# 282_Universal_Verteilerplatine_ALF_v1_0_.net
KiCad netlist of a schematic drawn in EAGLE
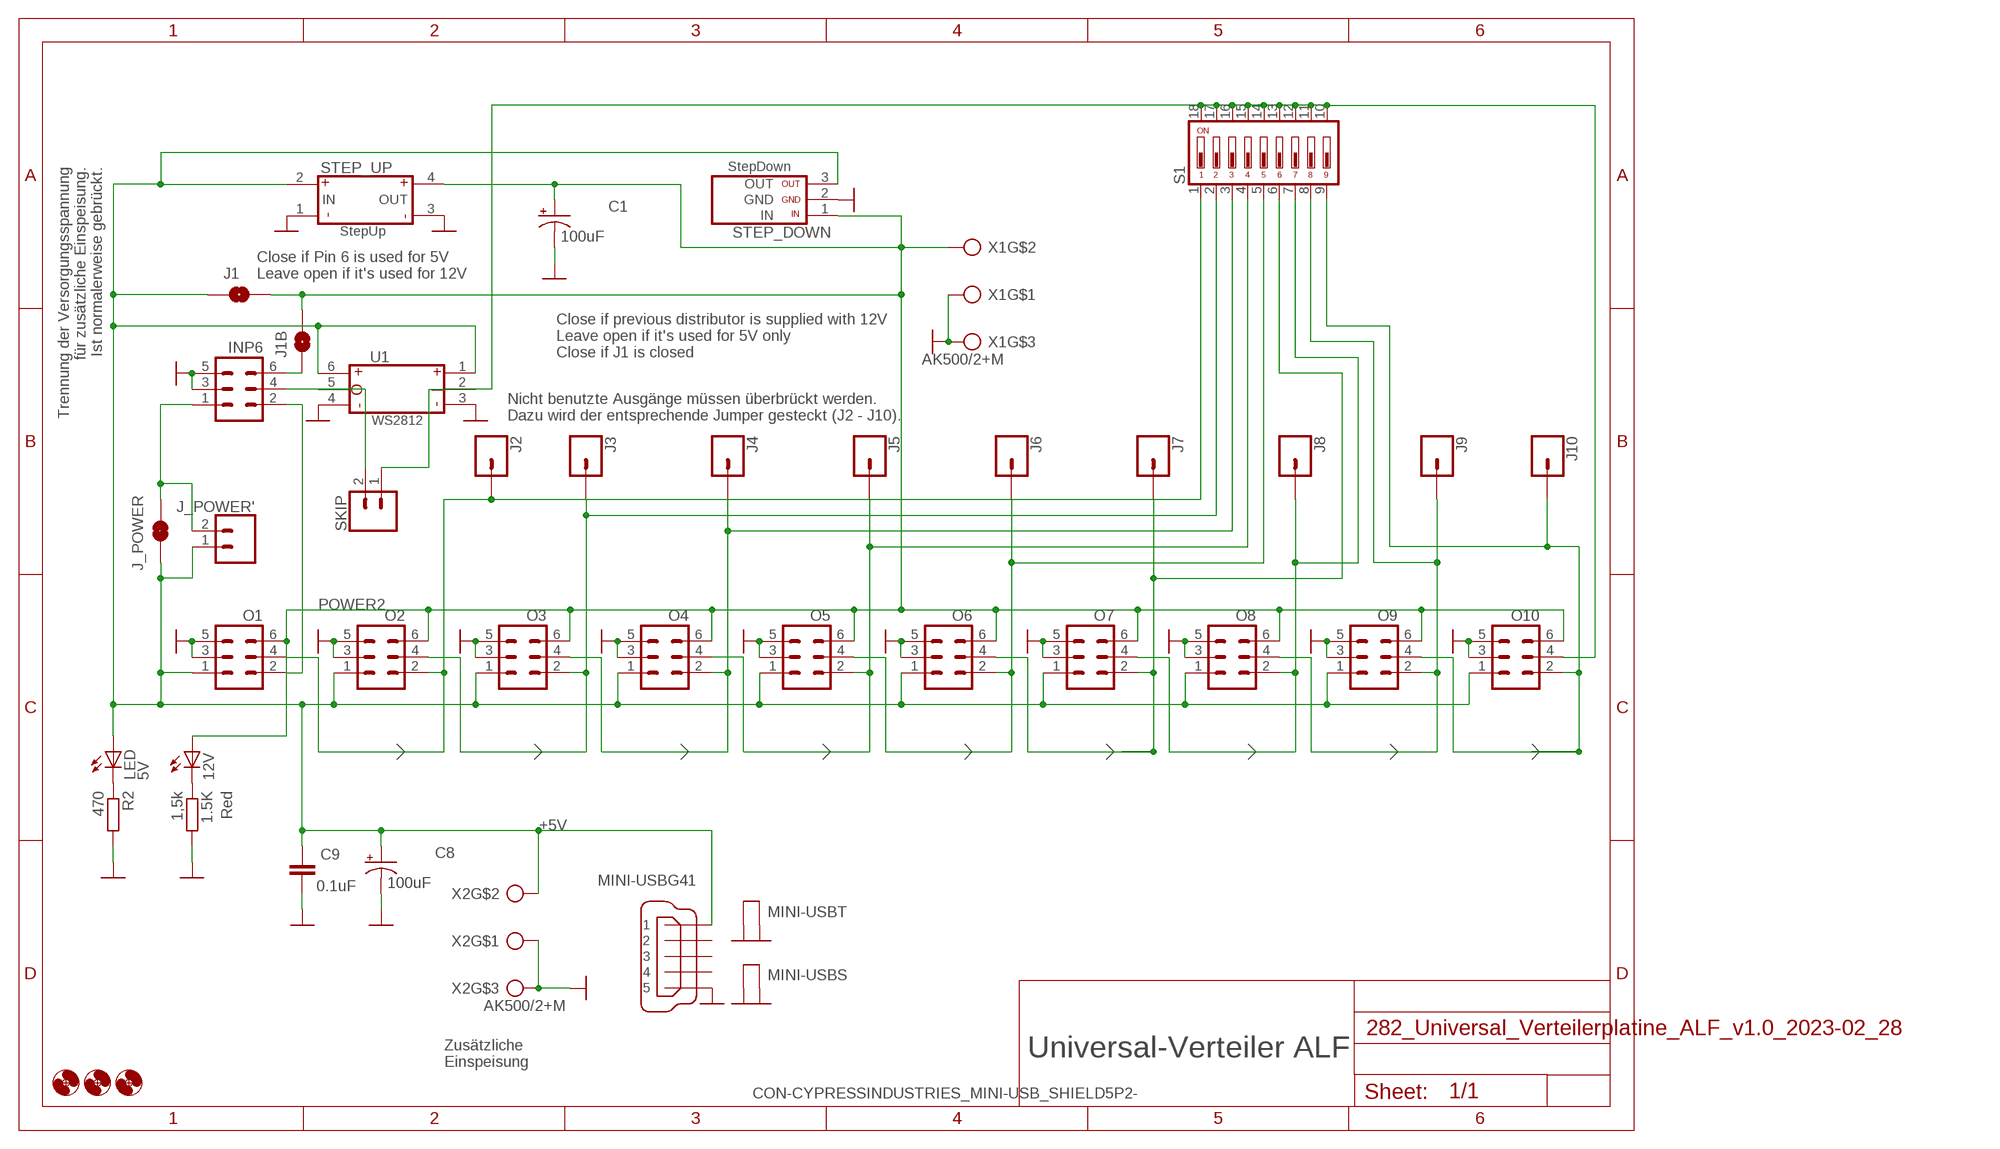
[diagram p0: schematic, sheet 1]

(export (version "E")
  (design (tool "Eeschema 10.0.6"))
  (components
    (comp (ref "1.5K")
      (value "1,5k")
      (footprint "eagle-import:RCL_0207_7")
      (libsource (lib "eagle-import") (part "RCL_R-EU_0207/7"))
    )
    (comp (ref "12V")
      (value "Red")
      (footprint "eagle-import:LED_LED3MM")
      (libsource (lib "eagle-import") (part "LED_LED3MM"))
    )
    (comp (ref "C1")
      (value "100uF")
      (footprint "eagle-import:SPARKFUN-CAPACITORS_CPOL-RADIAL-100UF-25V")
      (libsource (lib "eagle-import") (part "SPARKFUN-CAPACITORS_100UF-25V-20%(PTH)"))
    )
    (comp (ref "C8")
      (value "100uF")
      (footprint "eagle-import:SPARKFUN-CAPACITORS_CPOL-RADIAL-100UF-25V")
      (libsource (lib "eagle-import") (part "SPARKFUN-CAPACITORS_100UF-25V-20%(PTH)"))
    )
    (comp (ref "C9")
      (value "0.1uF")
      (footprint "eagle-import:C025-025X050")
      (libsource (lib "eagle-import") (part "C-EU025-025X050"))
    )
    (comp (ref "H5")
      (value "MOUNT-HOLE3.0")
      (footprint "eagle-import:3,0")
      (libsource (lib "eagle-import") (part "MOUNT-HOLE3.0"))
    )
    (comp (ref "H6")
      (value "MOUNT-HOLE3.0")
      (footprint "eagle-import:3,0")
      (libsource (lib "eagle-import") (part "MOUNT-HOLE3.0"))
    )
    (comp (ref "H8")
      (value "MOUNT-HOLE3.0")
      (footprint "eagle-import:3,0")
      (libsource (lib "eagle-import") (part "MOUNT-HOLE3.0"))
    )
    (comp (ref "INP6")
      (value "ML6")
      (footprint "eagle-import:ML6")
      (libsource (lib "eagle-import") (part "ML6"))
    )
    (comp (ref "J1")
      (value "SOLDERJUMPERNO")
      (footprint "eagle-import:SJ_2S-NO")
      (libsource (lib "eagle-import") (part "SOLDERJUMPERNO"))
    )
    (comp (ref "J1B")
      (value "SOLDERJUMPERNO")
      (footprint "eagle-import:SJ_2S-NO")
      (libsource (lib "eagle-import") (part "SOLDERJUMPERNO"))
    )
    (comp (ref "J2")
      (value "CONN_01_NO_BORDER")
      (footprint "eagle-import:1X01_NO_BORDER")
      (libsource (lib "eagle-import") (part "CONN_01_NO_BORDER"))
    )
    (comp (ref "J3")
      (value "CONN_01_NO_BORDER")
      (footprint "eagle-import:1X01_NO_BORDER")
      (libsource (lib "eagle-import") (part "CONN_01_NO_BORDER"))
    )
    (comp (ref "J4")
      (value "CONN_01_NO_BORDER")
      (footprint "eagle-import:1X01_NO_BORDER")
      (libsource (lib "eagle-import") (part "CONN_01_NO_BORDER"))
    )
    (comp (ref "J5")
      (value "CONN_01_NO_BORDER")
      (footprint "eagle-import:1X01_NO_BORDER")
      (libsource (lib "eagle-import") (part "CONN_01_NO_BORDER"))
    )
    (comp (ref "J6")
      (value "CONN_01_NO_BORDER")
      (footprint "eagle-import:1X01_NO_BORDER")
      (libsource (lib "eagle-import") (part "CONN_01_NO_BORDER"))
    )
    (comp (ref "J7")
      (value "CONN_01_NO_BORDER")
      (footprint "eagle-import:1X01_NO_BORDER")
      (libsource (lib "eagle-import") (part "CONN_01_NO_BORDER"))
    )
    (comp (ref "J8")
      (value "CONN_01_NO_BORDER")
      (footprint "eagle-import:1X01_NO_BORDER")
      (libsource (lib "eagle-import") (part "CONN_01_NO_BORDER"))
    )
    (comp (ref "J9")
      (value "CONN_01_NO_BORDER")
      (footprint "eagle-import:1X01_NO_BORDER")
      (libsource (lib "eagle-import") (part "CONN_01_NO_BORDER"))
    )
    (comp (ref "J10")
      (value "CONN_01_NO_BORDER")
      (footprint "eagle-import:1X01_NO_BORDER")
      (libsource (lib "eagle-import") (part "CONN_01_NO_BORDER"))
    )
    (comp (ref "J_POWER")
      (value "SOLDERJUMPERNO")
      (footprint "eagle-import:SJ_2S-NO")
      (libsource (lib "eagle-import") (part "SOLDERJUMPERNO"))
    )
    (comp (ref "J_POWER'")
      (value "CONN_02")
      (footprint "eagle-import:1X02")
      (libsource (lib "eagle-import") (part "CONN_02"))
    )
    (comp (ref "LED")
      (value "5V")
      (footprint "eagle-import:LED_LED3MM")
      (libsource (lib "eagle-import") (part "LED_LED3MM"))
    )
    (comp (ref "MINI-USB")
      (value "CON-CYPRESSINDUSTRIES_MINI-USB_SHIELD5P2-")
      (footprint "eagle-import:MINI_USB_MULTI")
      (libsource (lib "eagle-import") (part "CON-CYPRESSINDUSTRIES_MINI-USB_SHIELD5P2-"))
    )
    (comp (ref "O1")
      (value "ML6")
      (footprint "eagle-import:ML6")
      (libsource (lib "eagle-import") (part "ML6"))
    )
    (comp (ref "O2")
      (value "ML6")
      (footprint "eagle-import:ML6")
      (libsource (lib "eagle-import") (part "ML6"))
    )
    (comp (ref "O3")
      (value "ML6")
      (footprint "eagle-import:ML6")
      (libsource (lib "eagle-import") (part "ML6"))
    )
    (comp (ref "O4")
      (value "ML6")
      (footprint "eagle-import:ML6")
      (libsource (lib "eagle-import") (part "ML6"))
    )
    (comp (ref "O5")
      (value "ML6")
      (footprint "eagle-import:ML6")
      (libsource (lib "eagle-import") (part "ML6"))
    )
    (comp (ref "O6")
      (value "ML6")
      (footprint "eagle-import:ML6")
      (libsource (lib "eagle-import") (part "ML6"))
    )
    (comp (ref "O7")
      (value "ML6")
      (footprint "eagle-import:ML6")
      (libsource (lib "eagle-import") (part "ML6"))
    )
    (comp (ref "O8")
      (value "ML6")
      (footprint "eagle-import:ML6")
      (libsource (lib "eagle-import") (part "ML6"))
    )
    (comp (ref "O9")
      (value "ML6")
      (footprint "eagle-import:ML6")
      (libsource (lib "eagle-import") (part "ML6"))
    )
    (comp (ref "O10")
      (value "ML6")
      (footprint "eagle-import:ML6")
      (libsource (lib "eagle-import") (part "ML6"))
    )
    (comp (ref "R2")
      (value "470")
      (footprint "eagle-import:RCL_0207_7")
      (libsource (lib "eagle-import") (part "RCL_R-EU_0207/7"))
    )
    (comp (ref "S1")
      (value "DIP09YL")
      (footprint "eagle-import:DIP09YL")
      (libsource (lib "eagle-import") (part "DIP09YL"))
    )
    (comp (ref "SKIP")
      (value "CONN_02")
      (footprint "eagle-import:1X02")
      (libsource (lib "eagle-import") (part "CONN_02"))
    )
    (comp (ref "STEP_DOWN")
      (value "STEP_DOWN")
      (footprint "eagle-import:MINI_STEP_DOWN")
      (libsource (lib "eagle-import") (part "STEP_DOWN"))
    )
    (comp (ref "STEP_UP")
      (value "STEP_UP")
      (footprint "eagle-import:MINI_STEP_UP")
      (libsource (lib "eagle-import") (part "STEP_UP"))
    )
    (comp (ref "U1")
      (value "WS2812_BREAKOUTCUT")
      (footprint "eagle-import:WS2812__BREAKOUT_CUT")
      (libsource (lib "eagle-import") (part "WS2812_BREAKOUTCUT"))
    )
    (comp (ref "X1")
      (value "AK500/2+M")
      (footprint "eagle-import:AK500_2+M")
      (libsource (lib "eagle-import") (part "AK500/2+M"))
    )
    (comp (ref "X2")
      (value "AK500/2+M")
      (footprint "eagle-import:AK500_2+M")
      (libsource (lib "eagle-import") (part "AK500/2+M"))
    )
  )
  (nets
    (net (code "1") (name "/POWER2") (class "Default")
      (node (ref "12V") (pin "A") (pinfunction "A_A") (pintype "passive"))
      (node (ref "C1") (pin "1") (pinfunction "+_1") (pintype "passive"))
      (node (ref "J1") (pin "2") (pinfunction "2_2") (pintype "passive"))
      (node (ref "J1B") (pin "2") (pinfunction "2_2") (pintype "passive"))
      (node (ref "O1") (pin "6") (pinfunction "6_6") (pintype "passive"))
      (node (ref "O10") (pin "6") (pinfunction "6_6") (pintype "passive"))
      (node (ref "O2") (pin "6") (pinfunction "6_6") (pintype "passive"))
      (node (ref "O3") (pin "6") (pinfunction "6_6") (pintype "passive"))
      (node (ref "O4") (pin "6") (pinfunction "6_6") (pintype "passive"))
      (node (ref "O5") (pin "6") (pinfunction "6_6") (pintype "passive"))
      (node (ref "O6") (pin "6") (pinfunction "6_6") (pintype "passive"))
      (node (ref "O7") (pin "6") (pinfunction "6_6") (pintype "passive"))
      (node (ref "O8") (pin "6") (pinfunction "6_6") (pintype "passive"))
      (node (ref "O9") (pin "6") (pinfunction "6_6") (pintype "passive"))
      (node (ref "STEP_DOWN") (pin "1") (pinfunction "VDD_IN_1") (pintype "passive"))
      (node (ref "STEP_UP") (pin "4") (pinfunction "VDD_OUT_4") (pintype "passive"))
      (node (ref "X1") (pin "2") (pinfunction "KL_2") (pintype "passive"))
    )
    (net (code "2") (name "GND") (class "Default")
      (node (ref "1.5K") (pin "2") (pinfunction "2_2") (pintype "passive"))
      (node (ref "C1") (pin "2") (pinfunction "-_2") (pintype "passive"))
      (node (ref "C8") (pin "2") (pinfunction "-_2") (pintype "passive"))
      (node (ref "C9") (pin "1") (pinfunction "1_1") (pintype "passive"))
      (node (ref "INP6") (pin "3") (pinfunction "3_3") (pintype "passive"))
      (node (ref "INP6") (pin "5") (pinfunction "5_5") (pintype "passive"))
      (node (ref "MINI-USB") (pin "5") (pinfunction "5_5") (pintype "passive"))
      (node (ref "MINI-USB") (pin "M1") (pinfunction "S1_M1") (pintype "passive"))
      (node (ref "MINI-USB") (pin "M2") (pinfunction "S2_M2") (pintype "passive"))
      (node (ref "MINI-USB") (pin "M3") (pinfunction "S1_M3") (pintype "passive"))
      (node (ref "MINI-USB") (pin "M4") (pinfunction "S2_M4") (pintype "passive"))
      (node (ref "O1") (pin "3") (pinfunction "3_3") (pintype "passive"))
      (node (ref "O1") (pin "5") (pinfunction "5_5") (pintype "passive"))
      (node (ref "O10") (pin "3") (pinfunction "3_3") (pintype "passive"))
      (node (ref "O10") (pin "5") (pinfunction "5_5") (pintype "passive"))
      (node (ref "O2") (pin "3") (pinfunction "3_3") (pintype "passive"))
      (node (ref "O2") (pin "5") (pinfunction "5_5") (pintype "passive"))
      (node (ref "O3") (pin "3") (pinfunction "3_3") (pintype "passive"))
      (node (ref "O3") (pin "5") (pinfunction "5_5") (pintype "passive"))
      (node (ref "O4") (pin "3") (pinfunction "3_3") (pintype "passive"))
      (node (ref "O4") (pin "5") (pinfunction "5_5") (pintype "passive"))
      (node (ref "O5") (pin "3") (pinfunction "3_3") (pintype "passive"))
      (node (ref "O5") (pin "5") (pinfunction "5_5") (pintype "passive"))
      (node (ref "O6") (pin "3") (pinfunction "3_3") (pintype "passive"))
      (node (ref "O6") (pin "5") (pinfunction "5_5") (pintype "passive"))
      (node (ref "O7") (pin "3") (pinfunction "3_3") (pintype "passive"))
      (node (ref "O7") (pin "5") (pinfunction "5_5") (pintype "passive"))
      (node (ref "O8") (pin "3") (pinfunction "3_3") (pintype "passive"))
      (node (ref "O8") (pin "5") (pinfunction "5_5") (pintype "passive"))
      (node (ref "O9") (pin "3") (pinfunction "3_3") (pintype "passive"))
      (node (ref "O9") (pin "5") (pinfunction "5_5") (pintype "passive"))
      (node (ref "R2") (pin "2") (pinfunction "2_2") (pintype "passive"))
      (node (ref "STEP_DOWN") (pin "2") (pinfunction "GND_2") (pintype "passive"))
      (node (ref "STEP_UP") (pin "1") (pinfunction "GND_IN_1") (pintype "passive"))
      (node (ref "STEP_UP") (pin "3") (pinfunction "GND_OUT_3") (pintype "passive"))
      (node (ref "U1") (pin "3") (pinfunction "GND1_3") (pintype "passive"))
      (node (ref "U1") (pin "4") (pinfunction "GND_4") (pintype "passive"))
      (node (ref "X1") (pin "1") (pinfunction "KL_1") (pintype "passive"))
      (node (ref "X1") (pin "M") (pinfunction "KL_M") (pintype "passive"))
      (node (ref "X2") (pin "1") (pinfunction "KL_1") (pintype "passive"))
      (node (ref "X2") (pin "M") (pinfunction "KL_M") (pintype "passive"))
    )
    (net (code "3") (name "Net-(12V-C)") (class "Default")
      (node (ref "1.5K") (pin "1") (pinfunction "1_1") (pintype "passive"))
      (node (ref "12V") (pin "K") (pinfunction "C_K") (pintype "passive"))
    )
    (net (code "4") (name "Net-(C8-+)") (class "Default")
      (node (ref "C8") (pin "1") (pinfunction "+_1") (pintype "passive"))
      (node (ref "C9") (pin "2") (pinfunction "2_2") (pintype "passive"))
      (node (ref "J1") (pin "1") (pinfunction "1_1") (pintype "passive"))
      (node (ref "J_POWER") (pin "1") (pinfunction "1_1") (pintype "passive"))
      (node (ref "J_POWER'") (pin "1") (pinfunction "1_1") (pintype "passive"))
      (node (ref "LED") (pin "A") (pinfunction "A_A") (pintype "passive"))
      (node (ref "MINI-USB") (pin "1") (pinfunction "1_1") (pintype "passive"))
      (node (ref "O1") (pin "1") (pinfunction "1_1") (pintype "passive"))
      (node (ref "O10") (pin "1") (pinfunction "1_1") (pintype "passive"))
      (node (ref "O2") (pin "1") (pinfunction "1_1") (pintype "passive"))
      (node (ref "O3") (pin "1") (pinfunction "1_1") (pintype "passive"))
      (node (ref "O4") (pin "1") (pinfunction "1_1") (pintype "passive"))
      (node (ref "O5") (pin "1") (pinfunction "1_1") (pintype "passive"))
      (node (ref "O6") (pin "1") (pinfunction "1_1") (pintype "passive"))
      (node (ref "O7") (pin "1") (pinfunction "1_1") (pintype "passive"))
      (node (ref "O8") (pin "1") (pinfunction "1_1") (pintype "passive"))
      (node (ref "O9") (pin "1") (pinfunction "1_1") (pintype "passive"))
      (node (ref "STEP_DOWN") (pin "3") (pinfunction "VDD_OUT_3") (pintype "passive"))
      (node (ref "STEP_UP") (pin "2") (pinfunction "VDD_IN_2") (pintype "passive"))
      (node (ref "U1") (pin "1") (pinfunction "VDD1_1") (pintype "passive"))
      (node (ref "U1") (pin "6") (pinfunction "VDD_6") (pintype "passive"))
      (node (ref "X2") (pin "2") (pinfunction "KL_2") (pintype "passive"))
    )
    (net (code "5") (name "Net-(INP6-Pad1)") (class "Default")
      (node (ref "INP6") (pin "1") (pinfunction "1_1") (pintype "passive"))
      (node (ref "J_POWER") (pin "2") (pinfunction "2_2") (pintype "passive"))
      (node (ref "J_POWER'") (pin "2") (pinfunction "2_2") (pintype "passive"))
    )
    (net (code "6") (name "Net-(INP6-Pad2)") (class "Default")
      (node (ref "INP6") (pin "2") (pinfunction "2_2") (pintype "passive"))
      (node (ref "O1") (pin "2") (pinfunction "2_2") (pintype "passive"))
    )
    (net (code "7") (name "Net-(INP6-Pad6)") (class "Default")
      (node (ref "INP6") (pin "6") (pinfunction "6_6") (pintype "passive"))
      (node (ref "J1B") (pin "1") (pinfunction "1_1") (pintype "passive"))
    )
    (net (code "8") (name "Net-(J2-Pad1)") (class "Default")
      (node (ref "J2") (pin "1") (pinfunction "1_1") (pintype "passive"))
      (node (ref "O1") (pin "4") (pinfunction "4_4") (pintype "passive"))
      (node (ref "O2") (pin "2") (pinfunction "2_2") (pintype "passive"))
      (node (ref "S1") (pin "1") (pinfunction "1_1") (pintype "passive"))
    )
    (net (code "9") (name "Net-(J3-Pad1)") (class "Default")
      (node (ref "J3") (pin "1") (pinfunction "1_1") (pintype "passive"))
      (node (ref "O2") (pin "4") (pinfunction "4_4") (pintype "passive"))
      (node (ref "O3") (pin "2") (pinfunction "2_2") (pintype "passive"))
      (node (ref "S1") (pin "2") (pinfunction "2_2") (pintype "passive"))
    )
    (net (code "10") (name "Net-(J4-Pad1)") (class "Default")
      (node (ref "J4") (pin "1") (pinfunction "1_1") (pintype "passive"))
      (node (ref "O3") (pin "4") (pinfunction "4_4") (pintype "passive"))
      (node (ref "O4") (pin "2") (pinfunction "2_2") (pintype "passive"))
      (node (ref "S1") (pin "3") (pinfunction "3_3") (pintype "passive"))
    )
    (net (code "11") (name "Net-(J5-Pad1)") (class "Default")
      (node (ref "J5") (pin "1") (pinfunction "1_1") (pintype "passive"))
      (node (ref "O4") (pin "4") (pinfunction "4_4") (pintype "passive"))
      (node (ref "O5") (pin "2") (pinfunction "2_2") (pintype "passive"))
      (node (ref "S1") (pin "4") (pinfunction "4_4") (pintype "passive"))
    )
    (net (code "12") (name "Net-(J6-Pad1)") (class "Default")
      (node (ref "J6") (pin "1") (pinfunction "1_1") (pintype "passive"))
      (node (ref "O5") (pin "4") (pinfunction "4_4") (pintype "passive"))
      (node (ref "O6") (pin "2") (pinfunction "2_2") (pintype "passive"))
      (node (ref "S1") (pin "5") (pinfunction "5_5") (pintype "passive"))
    )
    (net (code "13") (name "Net-(J7-Pad1)") (class "Default")
      (node (ref "J7") (pin "1") (pinfunction "1_1") (pintype "passive"))
      (node (ref "O6") (pin "4") (pinfunction "4_4") (pintype "passive"))
      (node (ref "O7") (pin "2") (pinfunction "2_2") (pintype "passive"))
      (node (ref "S1") (pin "6") (pinfunction "6_6") (pintype "passive"))
    )
    (net (code "14") (name "Net-(J8-Pad1)") (class "Default")
      (node (ref "J8") (pin "1") (pinfunction "1_1") (pintype "passive"))
      (node (ref "O7") (pin "4") (pinfunction "4_4") (pintype "passive"))
      (node (ref "O8") (pin "2") (pinfunction "2_2") (pintype "passive"))
      (node (ref "S1") (pin "7") (pinfunction "7_7") (pintype "passive"))
    )
    (net (code "15") (name "Net-(J9-Pad1)") (class "Default")
      (node (ref "J9") (pin "1") (pinfunction "1_1") (pintype "passive"))
      (node (ref "O8") (pin "4") (pinfunction "4_4") (pintype "passive"))
      (node (ref "O9") (pin "2") (pinfunction "2_2") (pintype "passive"))
      (node (ref "S1") (pin "8") (pinfunction "8_8") (pintype "passive"))
    )
    (net (code "16") (name "Net-(J10-Pad1)") (class "Default")
      (node (ref "J10") (pin "1") (pinfunction "1_1") (pintype "passive"))
      (node (ref "O10") (pin "2") (pinfunction "2_2") (pintype "passive"))
      (node (ref "O9") (pin "4") (pinfunction "4_4") (pintype "passive"))
      (node (ref "S1") (pin "9") (pinfunction "9_9") (pintype "passive"))
    )
    (net (code "17") (name "Net-(LED-C)") (class "Default")
      (node (ref "LED") (pin "K") (pinfunction "C_K") (pintype "passive"))
      (node (ref "R2") (pin "1") (pinfunction "1_1") (pintype "passive"))
    )
    (net (code "18") (name "Net-(U1-DIN)") (class "Default")
      (node (ref "O10") (pin "4") (pinfunction "4_4") (pintype "passive"))
      (node (ref "S1") (pin "10") (pinfunction "10_10") (pintype "passive"))
      (node (ref "S1") (pin "11") (pinfunction "11_11") (pintype "passive"))
      (node (ref "S1") (pin "12") (pinfunction "12_12") (pintype "passive"))
      (node (ref "S1") (pin "13") (pinfunction "13_13") (pintype "passive"))
      (node (ref "S1") (pin "14") (pinfunction "14_14") (pintype "passive"))
      (node (ref "S1") (pin "15") (pinfunction "15_15") (pintype "passive"))
      (node (ref "S1") (pin "16") (pinfunction "16_16") (pintype "passive"))
      (node (ref "S1") (pin "17") (pinfunction "17_17") (pintype "passive"))
      (node (ref "S1") (pin "18") (pinfunction "18_18") (pintype "passive"))
      (node (ref "SKIP") (pin "1") (pinfunction "1_1") (pintype "passive"))
      (node (ref "U1") (pin "2") (pinfunction "DIN_2") (pintype "passive"))
    )
    (net (code "19") (name "Net-(U1-DO)") (class "Default")
      (node (ref "INP6") (pin "4") (pinfunction "4_4") (pintype "passive"))
      (node (ref "SKIP") (pin "2") (pinfunction "2_2") (pintype "passive"))
      (node (ref "U1") (pin "5") (pinfunction "DO_5") (pintype "passive"))
    )
    (net (code "20") (name "unconnected-(MINI-USB-Pad2)") (class "Default")
      (node (ref "MINI-USB") (pin "2") (pinfunction "2_2") (pintype "passive"))
    )
    (net (code "21") (name "unconnected-(MINI-USB-Pad3)") (class "Default")
      (node (ref "MINI-USB") (pin "3") (pinfunction "3_3") (pintype "passive"))
    )
    (net (code "22") (name "unconnected-(MINI-USB-Pad4)") (class "Default")
      (node (ref "MINI-USB") (pin "4") (pinfunction "4_4") (pintype "passive"))
    )
  )
)
